# 8Bit_Register_Right.net
KiCad netlist of a schematic drawn in EAGLE
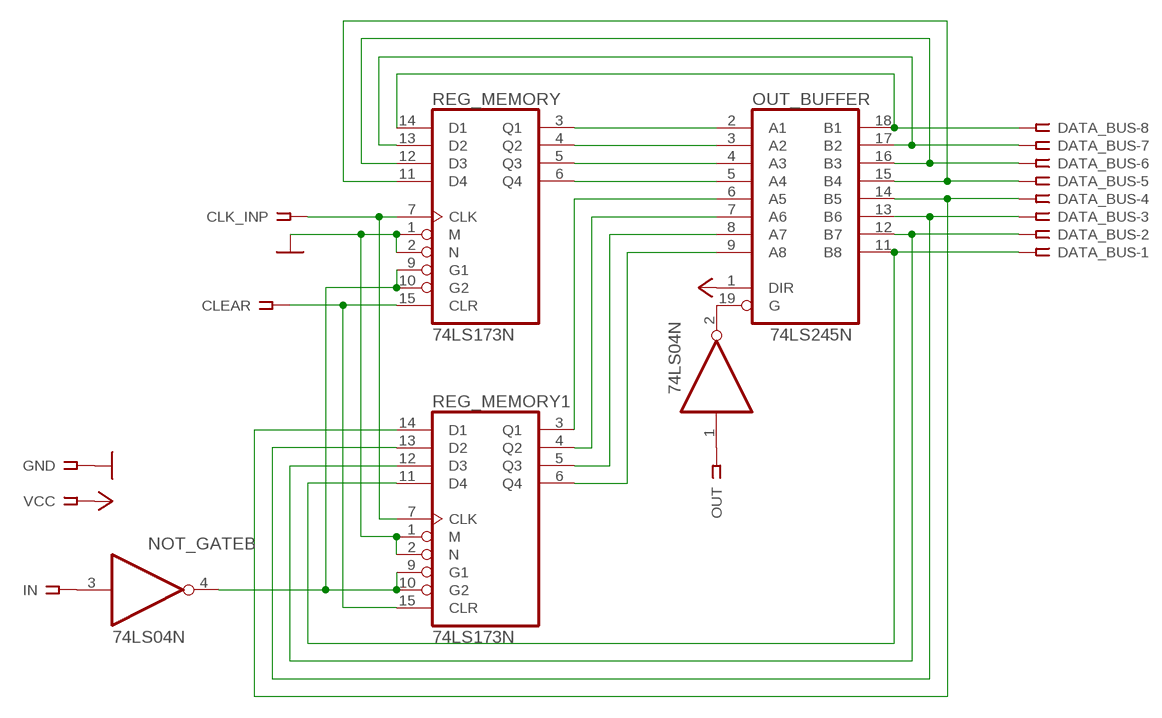
[diagram p0: schematic, sheet 1]

(export (version "E")
  (design (tool "Eeschema 10.0.6"))
  (components
    (comp (ref "CLEAR")
      (value "SSW-101-02-G-S-RA")
      (footprint "eagle-import:SSW-101-02-G-S-RA")
      (fields (field (name "MF") "Samtec Inc."))
      (libsource (lib "eagle-import") (part "SSW-101-02-G-S-RA"))
    )
    (comp (ref "CLK_INP")
      (value "SSW-101-02-G-S-RA")
      (footprint "eagle-import:SSW-101-02-G-S-RA")
      (fields (field (name "MF") "Samtec Inc."))
      (libsource (lib "eagle-import") (part "SSW-101-02-G-S-RA"))
    )
    (comp (ref "DATA_BUS")
      (value "SSW-108-02-G-S")
      (footprint "eagle-import:SSW-108-02-G-S")
      (fields (field (name "MF") "Samtec Inc."))
      (libsource (lib "eagle-import") (part "SSW-108-02-G-S"))
    )
    (comp (ref "GND")
      (value "SSW-101-02-G-S-RA")
      (footprint "eagle-import:SSW-101-02-G-S-RA")
      (fields (field (name "MF") "Samtec Inc."))
      (libsource (lib "eagle-import") (part "SSW-101-02-G-S-RA"))
    )
    (comp (ref "IN")
      (value "SSW-101-02-G-S-RA")
      (footprint "eagle-import:SSW-101-02-G-S-RA")
      (fields (field (name "MF") "Samtec Inc."))
      (libsource (lib "eagle-import") (part "SSW-101-02-G-S-RA"))
    )
    (comp (ref "NOT_GATE")
      (value "74LS04N")
      (footprint "eagle-import:DIL14")
      (libsource (lib "eagle-import") (part "7404NLS"))
    )
    (comp (ref "OUT")
      (value "SSW-101-02-G-S-RA")
      (footprint "eagle-import:SSW-101-02-G-S-RA")
      (fields (field (name "MF") "Samtec Inc."))
      (libsource (lib "eagle-import") (part "SSW-101-02-G-S-RA"))
    )
    (comp (ref "OUT_BUFFER")
      (value "74LS245N")
      (footprint "eagle-import:DIL20")
      (libsource (lib "eagle-import") (part "74245NLS"))
    )
    (comp (ref "REG_MEMORY")
      (value "74LS173N")
      (footprint "eagle-import:DIL16")
      (libsource (lib "eagle-import") (part "74173NLS"))
    )
    (comp (ref "REG_MEMORY1")
      (value "74LS173N")
      (footprint "eagle-import:DIL16")
      (libsource (lib "eagle-import") (part "74173NLS"))
    )
    (comp (ref "VCC")
      (value "SSW-101-02-G-S-RA")
      (footprint "eagle-import:SSW-101-02-G-S-RA")
      (fields (field (name "MF") "Samtec Inc."))
      (libsource (lib "eagle-import") (part "SSW-101-02-G-S-RA"))
    )
  )
  (nets
    (net (code "1") (name "GND") (class "Default")
      (node (ref "GND") (pin "1") (pinfunction "1_1") (pintype "passive"))
      (node (ref "REG_MEMORY") (pin "1") (pinfunction "M_1") (pintype "input"))
      (node (ref "REG_MEMORY") (pin "2") (pinfunction "N_2") (pintype "input"))
      (node (ref "REG_MEMORY1") (pin "1") (pinfunction "M_1") (pintype "input"))
      (node (ref "REG_MEMORY1") (pin "2") (pinfunction "N_2") (pintype "input"))
    )
    (net (code "2") (name "Net-(DATA_BUSB-1)") (class "Default")
      (node (ref "DATA_BUS") (pin "2") (pinfunction "1_2") (pintype "passive"))
      (node (ref "OUT_BUFFER") (pin "12") (pinfunction "B7_12") (pintype "bidirectional"))
      (node (ref "REG_MEMORY1") (pin "12") (pinfunction "D3_12") (pintype "input"))
    )
    (net (code "3") (name "Net-(DATA_BUSC-1)") (class "Default")
      (node (ref "DATA_BUS") (pin "3") (pinfunction "1_3") (pintype "passive"))
      (node (ref "OUT_BUFFER") (pin "13") (pinfunction "B6_13") (pintype "bidirectional"))
      (node (ref "REG_MEMORY1") (pin "13") (pinfunction "D2_13") (pintype "input"))
    )
    (net (code "4") (name "Net-(DATA_BUSD-1)") (class "Default")
      (node (ref "DATA_BUS") (pin "4") (pinfunction "1_4") (pintype "passive"))
      (node (ref "OUT_BUFFER") (pin "14") (pinfunction "B5_14") (pintype "bidirectional"))
      (node (ref "REG_MEMORY1") (pin "14") (pinfunction "D1_14") (pintype "input"))
    )
    (net (code "5") (name "Net-(DATA_BUSE-1)") (class "Default")
      (node (ref "DATA_BUS") (pin "5") (pinfunction "1_5") (pintype "passive"))
      (node (ref "OUT_BUFFER") (pin "15") (pinfunction "B4_15") (pintype "bidirectional"))
      (node (ref "REG_MEMORY") (pin "11") (pinfunction "D4_11") (pintype "input"))
    )
    (net (code "6") (name "Net-(DATA_BUSF-1)") (class "Default")
      (node (ref "DATA_BUS") (pin "6") (pinfunction "1_6") (pintype "passive"))
      (node (ref "OUT_BUFFER") (pin "16") (pinfunction "B3_16") (pintype "bidirectional"))
      (node (ref "REG_MEMORY") (pin "12") (pinfunction "D3_12") (pintype "input"))
    )
    (net (code "7") (name "Net-(DATA_BUSG-1)") (class "Default")
      (node (ref "DATA_BUS") (pin "7") (pinfunction "1_7") (pintype "passive"))
      (node (ref "OUT_BUFFER") (pin "17") (pinfunction "B2_17") (pintype "bidirectional"))
      (node (ref "REG_MEMORY") (pin "13") (pinfunction "D2_13") (pintype "input"))
    )
    (net (code "8") (name "Net-(DATA_BUSH-1)") (class "Default")
      (node (ref "DATA_BUS") (pin "8") (pinfunction "1_8") (pintype "passive"))
      (node (ref "OUT_BUFFER") (pin "18") (pinfunction "B1_18") (pintype "bidirectional"))
      (node (ref "REG_MEMORY") (pin "14") (pinfunction "D1_14") (pintype "input"))
    )
    (net (code "9") (name "Net-(NOT_GATEA-I)") (class "Default")
      (node (ref "NOT_GATE") (pin "1") (pinfunction "I_1") (pintype "input"))
      (node (ref "OUT") (pin "1") (pinfunction "1_1") (pintype "passive"))
    )
    (net (code "10") (name "Net-(NOT_GATEA-O)") (class "Default")
      (node (ref "NOT_GATE") (pin "2") (pinfunction "O_2") (pintype "output"))
      (node (ref "OUT_BUFFER") (pin "19") (pinfunction "G_19") (pintype "input"))
    )
    (net (code "11") (name "Net-(NOT_GATEB-I)") (class "Default")
      (node (ref "IN") (pin "1") (pinfunction "1_1") (pintype "passive"))
      (node (ref "NOT_GATE") (pin "3") (pinfunction "I_3") (pintype "input"))
    )
    (net (code "12") (name "Net-(NOT_GATEB-O)") (class "Default")
      (node (ref "NOT_GATE") (pin "4") (pinfunction "O_4") (pintype "output"))
      (node (ref "REG_MEMORY") (pin "10") (pinfunction "G2_10") (pintype "input"))
      (node (ref "REG_MEMORY") (pin "9") (pinfunction "G1_9") (pintype "input"))
      (node (ref "REG_MEMORY1") (pin "10") (pinfunction "G2_10") (pintype "input"))
      (node (ref "REG_MEMORY1") (pin "9") (pinfunction "G1_9") (pintype "input"))
    )
    (net (code "13") (name "Net-(OUT_BUFFERA-A1)") (class "Default")
      (node (ref "OUT_BUFFER") (pin "2") (pinfunction "A1_2") (pintype "bidirectional"))
      (node (ref "REG_MEMORY") (pin "3") (pinfunction "Q1_3") (pintype "tri_state"))
    )
    (net (code "14") (name "Net-(OUT_BUFFERA-A2)") (class "Default")
      (node (ref "OUT_BUFFER") (pin "3") (pinfunction "A2_3") (pintype "bidirectional"))
      (node (ref "REG_MEMORY") (pin "4") (pinfunction "Q2_4") (pintype "tri_state"))
    )
    (net (code "15") (name "Net-(OUT_BUFFERA-A3)") (class "Default")
      (node (ref "OUT_BUFFER") (pin "4") (pinfunction "A3_4") (pintype "bidirectional"))
      (node (ref "REG_MEMORY") (pin "5") (pinfunction "Q3_5") (pintype "tri_state"))
    )
    (net (code "16") (name "Net-(OUT_BUFFERA-A4)") (class "Default")
      (node (ref "OUT_BUFFER") (pin "5") (pinfunction "A4_5") (pintype "bidirectional"))
      (node (ref "REG_MEMORY") (pin "6") (pinfunction "Q4_6") (pintype "tri_state"))
    )
    (net (code "17") (name "Net-(OUT_BUFFERA-A5)") (class "Default")
      (node (ref "OUT_BUFFER") (pin "6") (pinfunction "A5_6") (pintype "bidirectional"))
      (node (ref "REG_MEMORY1") (pin "3") (pinfunction "Q1_3") (pintype "tri_state"))
    )
    (net (code "18") (name "Net-(OUT_BUFFERA-A6)") (class "Default")
      (node (ref "OUT_BUFFER") (pin "7") (pinfunction "A6_7") (pintype "bidirectional"))
      (node (ref "REG_MEMORY1") (pin "4") (pinfunction "Q2_4") (pintype "tri_state"))
    )
    (net (code "19") (name "Net-(OUT_BUFFERA-A7)") (class "Default")
      (node (ref "OUT_BUFFER") (pin "8") (pinfunction "A7_8") (pintype "bidirectional"))
      (node (ref "REG_MEMORY1") (pin "5") (pinfunction "Q3_5") (pintype "tri_state"))
    )
    (net (code "20") (name "Net-(OUT_BUFFERA-A8)") (class "Default")
      (node (ref "OUT_BUFFER") (pin "9") (pinfunction "A8_9") (pintype "bidirectional"))
      (node (ref "REG_MEMORY1") (pin "6") (pinfunction "Q4_6") (pintype "tri_state"))
    )
    (net (code "21") (name "Net-(OUT_BUFFERA-B8)") (class "Default")
      (node (ref "DATA_BUS") (pin "1") (pinfunction "1_1") (pintype "passive"))
      (node (ref "OUT_BUFFER") (pin "11") (pinfunction "B8_11") (pintype "bidirectional"))
      (node (ref "REG_MEMORY1") (pin "11") (pinfunction "D4_11") (pintype "input"))
    )
    (net (code "22") (name "Net-(REG_MEMORY1A-CLK)") (class "Default")
      (node (ref "CLK_INP") (pin "1") (pinfunction "1_1") (pintype "passive"))
      (node (ref "REG_MEMORY") (pin "7") (pinfunction "CLK_7") (pintype "input"))
      (node (ref "REG_MEMORY1") (pin "7") (pinfunction "CLK_7") (pintype "input"))
    )
    (net (code "23") (name "Net-(REG_MEMORY1A-CLR)") (class "Default")
      (node (ref "CLEAR") (pin "1") (pinfunction "1_1") (pintype "passive"))
      (node (ref "REG_MEMORY") (pin "15") (pinfunction "CLR_15") (pintype "input"))
      (node (ref "REG_MEMORY1") (pin "15") (pinfunction "CLR_15") (pintype "input"))
    )
    (net (code "24") (name "VCC") (class "Default")
      (node (ref "OUT_BUFFER") (pin "1") (pinfunction "DIR_1") (pintype "input"))
      (node (ref "VCC") (pin "1") (pinfunction "1_1") (pintype "passive"))
    )
  )
)
